# eth.net
KiCad netlist of a schematic drawn in Altium Designer
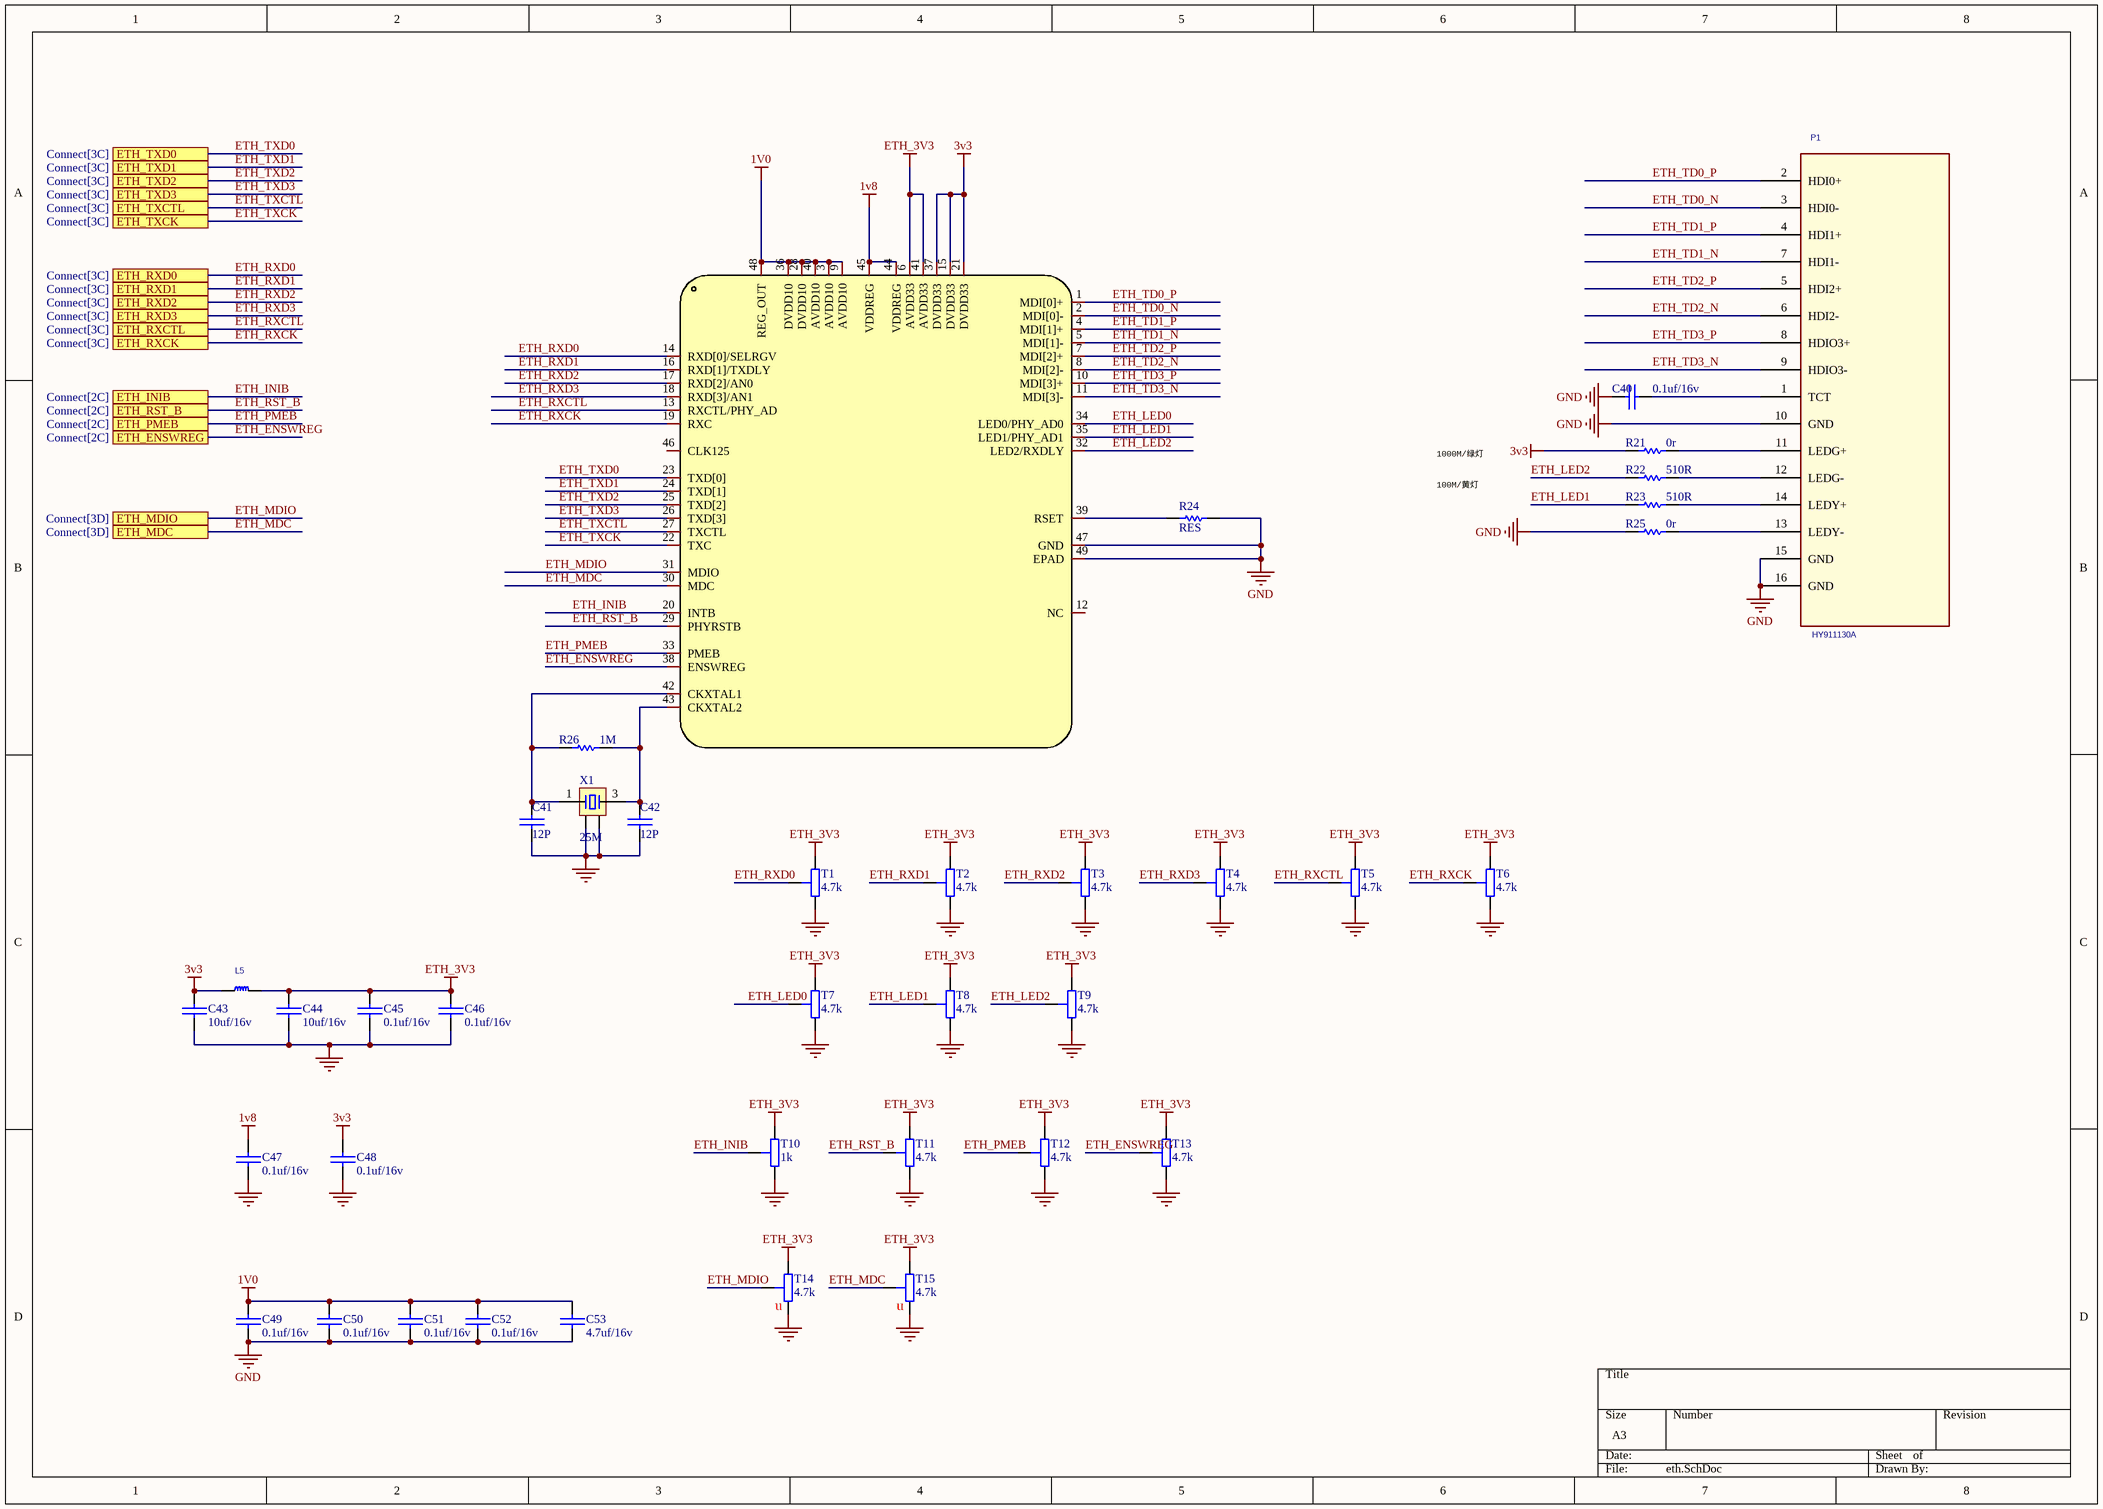
[diagram p0: eth.SchDoc]

(export (version "E")
  (design (tool "Eeschema 10.0.6"))
  (components
    (comp (ref "C40")
      (value "0.1uf/16v")
      (footprint "0402C")
      (description "无极性电容")
      (libsource (lib "1.00-阻容感") (part "CAP"))
    )
    (comp (ref "C41")
      (value "12P")
      (footprint "0402C")
      (description "无极性电容")
      (libsource (lib "1.00-阻容感") (part "CAP"))
    )
    (comp (ref "C42")
      (value "12P")
      (footprint "0402C")
      (description "无极性电容")
      (libsource (lib "1.00-阻容感") (part "CAP"))
    )
    (comp (ref "C43")
      (value "10uf/16v")
      (footprint "0402C")
      (description "无极性电容")
      (libsource (lib "1.00-阻容感") (part "CAP"))
    )
    (comp (ref "C44")
      (value "10uf/16v")
      (footprint "0402C")
      (description "无极性电容")
      (libsource (lib "1.00-阻容感") (part "CAP"))
    )
    (comp (ref "C45")
      (value "0.1uf/16v")
      (footprint "0402C")
      (description "无极性电容")
      (libsource (lib "1.00-阻容感") (part "CAP"))
    )
    (comp (ref "C46")
      (value "0.1uf/16v")
      (footprint "0402C")
      (description "无极性电容")
      (libsource (lib "1.00-阻容感") (part "CAP"))
    )
    (comp (ref "C47")
      (value "0.1uf/16v")
      (footprint "0402C")
      (description "无极性电容")
      (libsource (lib "1.00-阻容感") (part "CAP"))
    )
    (comp (ref "C48")
      (value "0.1uf/16v")
      (footprint "0402C")
      (description "无极性电容")
      (libsource (lib "1.00-阻容感") (part "CAP"))
    )
    (comp (ref "C49")
      (value "0.1uf/16v")
      (footprint "0402C")
      (description "无极性电容")
      (libsource (lib "1.00-阻容感") (part "CAP"))
    )
    (comp (ref "C50")
      (value "0.1uf/16v")
      (footprint "0402C")
      (description "无极性电容")
      (libsource (lib "1.00-阻容感") (part "CAP"))
    )
    (comp (ref "C51")
      (value "0.1uf/16v")
      (footprint "0402C")
      (description "无极性电容")
      (libsource (lib "1.00-阻容感") (part "CAP"))
    )
    (comp (ref "C52")
      (value "0.1uf/16v")
      (footprint "0402C")
      (description "无极性电容")
      (libsource (lib "1.00-阻容感") (part "CAP"))
    )
    (comp (ref "C53")
      (value "4.7uf/16v")
      (footprint "0402C")
      (description "无极性电容")
      (libsource (lib "1.00-阻容感") (part "CAP"))
    )
    (comp (ref "L5")
      (value "FB")
      (footprint "0402L")
      (description "铁氧体磁珠")
      (libsource (lib "1.00-阻容感") (part "FB"))
    )
    (comp (ref "P1")
      (value "HY911130A")
      (footprint "RJ45-TH_HR911130A")
      (description "RJ45")
      (libsource (lib "连接器插座") (part "HY911130A"))
    )
    (comp (ref "R21")
      (value "0r")
      (footprint "0402R")
      (description "电阻")
      (libsource (lib "1.00-阻容感") (part "RES"))
    )
    (comp (ref "R22")
      (value "510R")
      (footprint "0402R")
      (description "电阻")
      (libsource (lib "1.00-阻容感") (part "RES"))
    )
    (comp (ref "R23")
      (value "510R")
      (footprint "0402R")
      (description "电阻")
      (libsource (lib "1.00-阻容感") (part "RES"))
    )
    (comp (ref "R24")
      (value "RES")
      (footprint "0402R")
      (description "电阻")
      (libsource (lib "1.00-阻容感") (part "RES"))
    )
    (comp (ref "R25")
      (value "0r")
      (footprint "0402R")
      (description "电阻")
      (libsource (lib "1.00-阻容感") (part "RES"))
    )
    (comp (ref "R26")
      (value "1M")
      (footprint "0402R")
      (description "电阻")
      (libsource (lib "1.00-阻容感") (part "RES"))
    )
    (comp (ref "T1")
      (value "4.7k")
      (footprint "0402T")
      (description "调试")
      (libsource (lib "1.00-阻容感") (part "test"))
    )
    (comp (ref "T2")
      (value "4.7k")
      (footprint "0402T")
      (description "调试")
      (libsource (lib "1.00-阻容感") (part "test"))
    )
    (comp (ref "T3")
      (value "4.7k")
      (footprint "0402T")
      (description "调试")
      (libsource (lib "1.00-阻容感") (part "test"))
    )
    (comp (ref "T4")
      (value "4.7k")
      (footprint "0402T")
      (description "调试")
      (libsource (lib "1.00-阻容感") (part "test"))
    )
    (comp (ref "T5")
      (value "4.7k")
      (footprint "0402T")
      (description "调试")
      (libsource (lib "1.00-阻容感") (part "test"))
    )
    (comp (ref "T6")
      (value "4.7k")
      (footprint "0402T")
      (description "调试")
      (libsource (lib "1.00-阻容感") (part "test"))
    )
    (comp (ref "T7")
      (value "4.7k")
      (footprint "0402T")
      (description "调试")
      (libsource (lib "1.00-阻容感") (part "test"))
    )
    (comp (ref "T8")
      (value "4.7k")
      (footprint "0402T")
      (description "调试")
      (libsource (lib "1.00-阻容感") (part "test"))
    )
    (comp (ref "T9")
      (value "4.7k")
      (footprint "0402T")
      (description "调试")
      (libsource (lib "1.00-阻容感") (part "test"))
    )
    (comp (ref "T10")
      (value "1k")
      (footprint "0402T")
      (description "调试")
      (libsource (lib "1.00-阻容感") (part "test"))
    )
    (comp (ref "T11")
      (value "4.7k")
      (footprint "0402T")
      (description "调试")
      (libsource (lib "1.00-阻容感") (part "test"))
    )
    (comp (ref "T12")
      (value "4.7k")
      (footprint "0402T")
      (description "调试")
      (libsource (lib "1.00-阻容感") (part "test"))
    )
    (comp (ref "T13")
      (value "4.7k")
      (footprint "0402T")
      (description "调试")
      (libsource (lib "1.00-阻容感") (part "test"))
    )
    (comp (ref "T14")
      (value "4.7k")
      (footprint "0402T")
      (description "调试")
      (libsource (lib "1.00-阻容感") (part "test"))
    )
    (comp (ref "T15")
      (value "4.7k")
      (footprint "0402T")
      (description "调试")
      (libsource (lib "1.00-阻容感") (part "test"))
    )
    (comp (ref "U4")
      (value "RTL8211E-VB-CG")
      (footprint "QFN-48_L6.0-W6.0-P0.40-BL-EP3.8")
      (description "千兆以太网控制芯片")
      (fields (field (name "MANUFACTURER") "REALTEK(瑞昱)"))
      (libsource (lib "0.06-通讯IC") (part "RTL8211E-VB-CG"))
    )
    (comp (ref "X1")
      (value "25M")
      (footprint "OSC 3225-4P")
      (description "4脚无源晶振")
      (libsource (lib "6.01-晶振") (part "XTAL-4P"))
    )
  )
  (nets
    (net (code "1") (name "/ETH_ENSWREG") (class "Default")
      (node (ref "T13") (pin "1") (pinfunction "1_1") (pintype "passive"))
      (node (ref "U4") (pin "38") (pinfunction "ENSWREG_38") (pintype "passive"))
    )
    (net (code "2") (name "/ETH_INIB") (class "Default")
      (node (ref "T10") (pin "1") (pinfunction "1_1") (pintype "passive"))
      (node (ref "U4") (pin "20") (pinfunction "INTB_20") (pintype "passive"))
    )
    (net (code "3") (name "/ETH_LED0") (class "Default")
      (node (ref "T7") (pin "1") (pinfunction "1_1") (pintype "passive"))
      (node (ref "U4") (pin "34") (pinfunction "LED0/PHY_AD0_34") (pintype "passive"))
    )
    (net (code "4") (name "/ETH_LED1") (class "Default")
      (node (ref "R23") (pin "2") (pinfunction "2_2") (pintype "passive"))
      (node (ref "T8") (pin "1") (pinfunction "1_1") (pintype "passive"))
      (node (ref "U4") (pin "35") (pinfunction "LED1/PHY_AD1_35") (pintype "passive"))
    )
    (net (code "5") (name "/ETH_LED2") (class "Default")
      (node (ref "R22") (pin "2") (pinfunction "2_2") (pintype "passive"))
      (node (ref "T9") (pin "1") (pinfunction "1_1") (pintype "passive"))
      (node (ref "U4") (pin "32") (pinfunction "LED2/RXDLY_32") (pintype "passive"))
    )
    (net (code "6") (name "/ETH_MDC") (class "Default")
      (node (ref "T15") (pin "1") (pinfunction "1_1") (pintype "passive"))
      (node (ref "U4") (pin "30") (pinfunction "MDC_30") (pintype "passive"))
    )
    (net (code "7") (name "/ETH_MDIO") (class "Default")
      (node (ref "T14") (pin "1") (pinfunction "1_1") (pintype "passive"))
      (node (ref "U4") (pin "31") (pinfunction "MDIO_31") (pintype "passive"))
    )
    (net (code "8") (name "/ETH_PMEB") (class "Default")
      (node (ref "T12") (pin "1") (pinfunction "1_1") (pintype "passive"))
      (node (ref "U4") (pin "33") (pinfunction "PMEB_33") (pintype "passive"))
    )
    (net (code "9") (name "/ETH_RST_B") (class "Default")
      (node (ref "T11") (pin "1") (pinfunction "1_1") (pintype "passive"))
      (node (ref "U4") (pin "29") (pinfunction "PHYRSTB_29") (pintype "passive"))
    )
    (net (code "10") (name "/ETH_RXCK") (class "Default")
      (node (ref "T6") (pin "1") (pinfunction "1_1") (pintype "passive"))
      (node (ref "U4") (pin "19") (pinfunction "RXC_19") (pintype "passive"))
    )
    (net (code "11") (name "/ETH_RXCTL") (class "Default")
      (node (ref "T5") (pin "1") (pinfunction "1_1") (pintype "passive"))
      (node (ref "U4") (pin "13") (pinfunction "RXCTL/PHY_AD_13") (pintype "passive"))
    )
    (net (code "12") (name "/ETH_RXD0") (class "Default")
      (node (ref "T1") (pin "1") (pinfunction "1_1") (pintype "passive"))
      (node (ref "U4") (pin "14") (pinfunction "RXD[0]/SELRGV_14") (pintype "passive"))
    )
    (net (code "13") (name "/ETH_RXD1") (class "Default")
      (node (ref "T2") (pin "1") (pinfunction "1_1") (pintype "passive"))
      (node (ref "U4") (pin "16") (pinfunction "RXD[1]/TXDLY_16") (pintype "passive"))
    )
    (net (code "14") (name "/ETH_RXD2") (class "Default")
      (node (ref "T3") (pin "1") (pinfunction "1_1") (pintype "passive"))
      (node (ref "U4") (pin "17") (pinfunction "RXD[2]/AN0_17") (pintype "passive"))
    )
    (net (code "15") (name "/ETH_RXD3") (class "Default")
      (node (ref "T4") (pin "1") (pinfunction "1_1") (pintype "passive"))
      (node (ref "U4") (pin "18") (pinfunction "RXD[3]/AN1_18") (pintype "passive"))
    )
    (net (code "16") (name "/ETH_TD0_N") (class "Default")
      (node (ref "P1") (pin "3") (pinfunction "HDI0-_3") (pintype "passive"))
      (node (ref "U4") (pin "2") (pinfunction "MDI[0]-_2") (pintype "passive"))
    )
    (net (code "17") (name "/ETH_TD0_P") (class "Default")
      (node (ref "P1") (pin "2") (pinfunction "HDI0+_2") (pintype "passive"))
      (node (ref "U4") (pin "1") (pinfunction "MDI[0]+_1") (pintype "passive"))
    )
    (net (code "18") (name "/ETH_TD1_N") (class "Default")
      (node (ref "P1") (pin "7") (pinfunction "HDI1-_7") (pintype "passive"))
      (node (ref "U4") (pin "5") (pinfunction "MDI[1]-_5") (pintype "passive"))
    )
    (net (code "19") (name "/ETH_TD1_P") (class "Default")
      (node (ref "P1") (pin "4") (pinfunction "HDI1+_4") (pintype "passive"))
      (node (ref "U4") (pin "4") (pinfunction "MDI[1]+_4") (pintype "passive"))
    )
    (net (code "20") (name "/ETH_TD2_N") (class "Default")
      (node (ref "P1") (pin "6") (pinfunction "HDI2-_6") (pintype "passive"))
      (node (ref "U4") (pin "8") (pinfunction "MDI[2]-_8") (pintype "passive"))
    )
    (net (code "21") (name "/ETH_TD2_P") (class "Default")
      (node (ref "P1") (pin "5") (pinfunction "HDI2+_5") (pintype "passive"))
      (node (ref "U4") (pin "7") (pinfunction "MDI[2]+_7") (pintype "passive"))
    )
    (net (code "22") (name "/ETH_TD3_N") (class "Default")
      (node (ref "P1") (pin "9") (pinfunction "HDIO3-_9") (pintype "passive"))
      (node (ref "U4") (pin "11") (pinfunction "MDI[3]-_11") (pintype "passive"))
    )
    (net (code "23") (name "/ETH_TD3_P") (class "Default")
      (node (ref "P1") (pin "8") (pinfunction "HDIO3+_8") (pintype "passive"))
      (node (ref "U4") (pin "10") (pinfunction "MDI[3]+_10") (pintype "passive"))
    )
    (net (code "24") (name "/ETH_TXCK") (class "Default")
      (node (ref "U4") (pin "22") (pinfunction "TXC_22") (pintype "passive"))
    )
    (net (code "25") (name "/ETH_TXCTL") (class "Default")
      (node (ref "U4") (pin "27") (pinfunction "TXCTL_27") (pintype "passive"))
    )
    (net (code "26") (name "/ETH_TXD0") (class "Default")
      (node (ref "U4") (pin "23") (pinfunction "TXD[0]_23") (pintype "passive"))
    )
    (net (code "27") (name "/ETH_TXD1") (class "Default")
      (node (ref "U4") (pin "24") (pinfunction "TXD[1]_24") (pintype "passive"))
    )
    (net (code "28") (name "/ETH_TXD2") (class "Default")
      (node (ref "U4") (pin "25") (pinfunction "TXD[2]_25") (pintype "passive"))
    )
    (net (code "29") (name "/ETH_TXD3") (class "Default")
      (node (ref "U4") (pin "26") (pinfunction "TXD[3]_26") (pintype "passive"))
    )
    (net (code "30") (name "1V0") (class "Default")
      (node (ref "C49") (pin "2") (pinfunction "2_2") (pintype "passive"))
      (node (ref "C50") (pin "2") (pinfunction "2_2") (pintype "passive"))
      (node (ref "C51") (pin "2") (pinfunction "2_2") (pintype "passive"))
      (node (ref "C52") (pin "2") (pinfunction "2_2") (pintype "passive"))
      (node (ref "C53") (pin "2") (pinfunction "2_2") (pintype "passive"))
      (node (ref "U4") (pin "28") (pinfunction "DVDD10_28") (pintype "passive"))
      (node (ref "U4") (pin "3") (pinfunction "AVDD10_3") (pintype "passive"))
      (node (ref "U4") (pin "36") (pinfunction "DVDD10_36") (pintype "passive"))
      (node (ref "U4") (pin "40") (pinfunction "AVDD10_40") (pintype "passive"))
      (node (ref "U4") (pin "48") (pinfunction "REG_OUT_48") (pintype "passive"))
      (node (ref "U4") (pin "9") (pinfunction "AVDD10_9") (pintype "passive"))
    )
    (net (code "31") (name "1v8") (class "Default")
      (node (ref "C47") (pin "2") (pinfunction "2_2") (pintype "passive"))
      (node (ref "U4") (pin "44") (pinfunction "VDDREG_44") (pintype "passive"))
      (node (ref "U4") (pin "45") (pinfunction "VDDREG_45") (pintype "passive"))
    )
    (net (code "32") (name "3v3") (class "Default")
      (node (ref "C43") (pin "2") (pinfunction "2_2") (pintype "passive"))
      (node (ref "C48") (pin "2") (pinfunction "2_2") (pintype "passive"))
      (node (ref "L5") (pin "1") (pinfunction "1_1") (pintype "passive"))
      (node (ref "R21") (pin "2") (pinfunction "2_2") (pintype "passive"))
      (node (ref "U4") (pin "15") (pinfunction "DVDD33_15") (pintype "passive"))
      (node (ref "U4") (pin "21") (pinfunction "DVDD33_21") (pintype "passive"))
      (node (ref "U4") (pin "37") (pinfunction "DVDD33_37") (pintype "passive"))
    )
    (net (code "33") (name "ETH_3V3") (class "Default")
      (node (ref "C44") (pin "2") (pinfunction "2_2") (pintype "passive"))
      (node (ref "C45") (pin "2") (pinfunction "2_2") (pintype "passive"))
      (node (ref "C46") (pin "2") (pinfunction "2_2") (pintype "passive"))
      (node (ref "L5") (pin "2") (pinfunction "2_2") (pintype "passive"))
      (node (ref "T1") (pin "3") (pinfunction "3_3") (pintype "passive"))
      (node (ref "T10") (pin "3") (pinfunction "3_3") (pintype "passive"))
      (node (ref "T11") (pin "3") (pinfunction "3_3") (pintype "passive"))
      (node (ref "T12") (pin "3") (pinfunction "3_3") (pintype "passive"))
      (node (ref "T13") (pin "3") (pinfunction "3_3") (pintype "passive"))
      (node (ref "T14") (pin "3") (pinfunction "3_3") (pintype "passive"))
      (node (ref "T15") (pin "3") (pinfunction "3_3") (pintype "passive"))
      (node (ref "T2") (pin "3") (pinfunction "3_3") (pintype "passive"))
      (node (ref "T3") (pin "3") (pinfunction "3_3") (pintype "passive"))
      (node (ref "T4") (pin "3") (pinfunction "3_3") (pintype "passive"))
      (node (ref "T5") (pin "3") (pinfunction "3_3") (pintype "passive"))
      (node (ref "T6") (pin "3") (pinfunction "3_3") (pintype "passive"))
      (node (ref "T7") (pin "3") (pinfunction "3_3") (pintype "passive"))
      (node (ref "T8") (pin "3") (pinfunction "3_3") (pintype "passive"))
      (node (ref "T9") (pin "3") (pinfunction "3_3") (pintype "passive"))
      (node (ref "U4") (pin "41") (pinfunction "AVDD33_41") (pintype "passive"))
      (node (ref "U4") (pin "6") (pinfunction "AVDD33_6") (pintype "passive"))
    )
    (net (code "34") (name "GND") (class "Default")
      (node (ref "C40") (pin "2") (pinfunction "2_2") (pintype "passive"))
      (node (ref "C41") (pin "1") (pinfunction "1_1") (pintype "passive"))
      (node (ref "C42") (pin "1") (pinfunction "1_1") (pintype "passive"))
      (node (ref "C43") (pin "1") (pinfunction "1_1") (pintype "passive"))
      (node (ref "C44") (pin "1") (pinfunction "1_1") (pintype "passive"))
      (node (ref "C45") (pin "1") (pinfunction "1_1") (pintype "passive"))
      (node (ref "C46") (pin "1") (pinfunction "1_1") (pintype "passive"))
      (node (ref "C47") (pin "1") (pinfunction "1_1") (pintype "passive"))
      (node (ref "C48") (pin "1") (pinfunction "1_1") (pintype "passive"))
      (node (ref "C49") (pin "1") (pinfunction "1_1") (pintype "passive"))
      (node (ref "C50") (pin "1") (pinfunction "1_1") (pintype "passive"))
      (node (ref "C51") (pin "1") (pinfunction "1_1") (pintype "passive"))
      (node (ref "C52") (pin "1") (pinfunction "1_1") (pintype "passive"))
      (node (ref "C53") (pin "1") (pinfunction "1_1") (pintype "passive"))
      (node (ref "P1") (pin "10") (pinfunction "GND_10") (pintype "power_in"))
      (node (ref "P1") (pin "15") (pinfunction "GND_15") (pintype "power_in"))
      (node (ref "P1") (pin "16") (pinfunction "GND_16") (pintype "power_in"))
      (node (ref "R24") (pin "2") (pinfunction "2_2") (pintype "passive"))
      (node (ref "R25") (pin "2") (pinfunction "2_2") (pintype "passive"))
      (node (ref "T1") (pin "2") (pinfunction "2_2") (pintype "passive"))
      (node (ref "T10") (pin "2") (pinfunction "2_2") (pintype "passive"))
      (node (ref "T11") (pin "2") (pinfunction "2_2") (pintype "passive"))
      (node (ref "T12") (pin "2") (pinfunction "2_2") (pintype "passive"))
      (node (ref "T13") (pin "2") (pinfunction "2_2") (pintype "passive"))
      (node (ref "T14") (pin "2") (pinfunction "2_2") (pintype "passive"))
      (node (ref "T15") (pin "2") (pinfunction "2_2") (pintype "passive"))
      (node (ref "T2") (pin "2") (pinfunction "2_2") (pintype "passive"))
      (node (ref "T3") (pin "2") (pinfunction "2_2") (pintype "passive"))
      (node (ref "T4") (pin "2") (pinfunction "2_2") (pintype "passive"))
      (node (ref "T5") (pin "2") (pinfunction "2_2") (pintype "passive"))
      (node (ref "T6") (pin "2") (pinfunction "2_2") (pintype "passive"))
      (node (ref "T7") (pin "2") (pinfunction "2_2") (pintype "passive"))
      (node (ref "T8") (pin "2") (pinfunction "2_2") (pintype "passive"))
      (node (ref "T9") (pin "2") (pinfunction "2_2") (pintype "passive"))
      (node (ref "U4") (pin "47") (pinfunction "GND_47") (pintype "passive"))
      (node (ref "U4") (pin "49") (pinfunction "EPAD_49") (pintype "passive"))
      (node (ref "X1") (pin "2") (pinfunction "2_2") (pintype "passive"))
      (node (ref "X1") (pin "4") (pinfunction "4_4") (pintype "passive"))
    )
    (net (code "35") (name "Net-(P1-LEDG+)") (class "Default")
      (node (ref "P1") (pin "11") (pinfunction "LEDG+_11") (pintype "passive"))
      (node (ref "R21") (pin "1") (pinfunction "1_1") (pintype "passive"))
    )
    (net (code "36") (name "Net-(P1-LEDG-)") (class "Default")
      (node (ref "P1") (pin "12") (pinfunction "LEDG-_12") (pintype "passive"))
      (node (ref "R22") (pin "1") (pinfunction "1_1") (pintype "passive"))
    )
    (net (code "37") (name "Net-(P1-LEDY+)") (class "Default")
      (node (ref "P1") (pin "14") (pinfunction "LEDY+_14") (pintype "passive"))
      (node (ref "R23") (pin "1") (pinfunction "1_1") (pintype "passive"))
    )
    (net (code "38") (name "Net-(P1-LEDY-)") (class "Default")
      (node (ref "P1") (pin "13") (pinfunction "LEDY-_13") (pintype "passive"))
      (node (ref "R25") (pin "1") (pinfunction "1_1") (pintype "passive"))
    )
    (net (code "39") (name "Net-(P1-TCT)") (class "Default")
      (node (ref "C40") (pin "1") (pinfunction "1_1") (pintype "passive"))
      (node (ref "P1") (pin "1") (pinfunction "TCT_1") (pintype "passive"))
    )
    (net (code "40") (name "Net-(U4-CKXTAL1)") (class "Default")
      (node (ref "C41") (pin "2") (pinfunction "2_2") (pintype "passive"))
      (node (ref "R26") (pin "1") (pinfunction "1_1") (pintype "passive"))
      (node (ref "U4") (pin "42") (pinfunction "CKXTAL1_42") (pintype "passive"))
      (node (ref "X1") (pin "1") (pinfunction "1_1") (pintype "passive"))
    )
    (net (code "41") (name "Net-(U4-CKXTAL2)") (class "Default")
      (node (ref "C42") (pin "2") (pinfunction "2_2") (pintype "passive"))
      (node (ref "R26") (pin "2") (pinfunction "2_2") (pintype "passive"))
      (node (ref "U4") (pin "43") (pinfunction "CKXTAL2_43") (pintype "passive"))
      (node (ref "X1") (pin "3") (pinfunction "3_3") (pintype "passive"))
    )
    (net (code "42") (name "Net-(U4-RSET)") (class "Default")
      (node (ref "R24") (pin "1") (pinfunction "1_1") (pintype "passive"))
      (node (ref "U4") (pin "39") (pinfunction "RSET_39") (pintype "passive"))
    )
    (net (code "43") (name "unconnected-(U4-CLK125-Pad46)") (class "Default")
      (node (ref "U4") (pin "46") (pinfunction "CLK125_46") (pintype "passive"))
    )
    (net (code "44") (name "unconnected-(U4-NC-Pad12)") (class "Default")
      (node (ref "U4") (pin "12") (pinfunction "NC_12") (pintype "passive"))
    )
  )
)
